# rev16.net
KiCad netlist of a schematic drawn in EAGLE
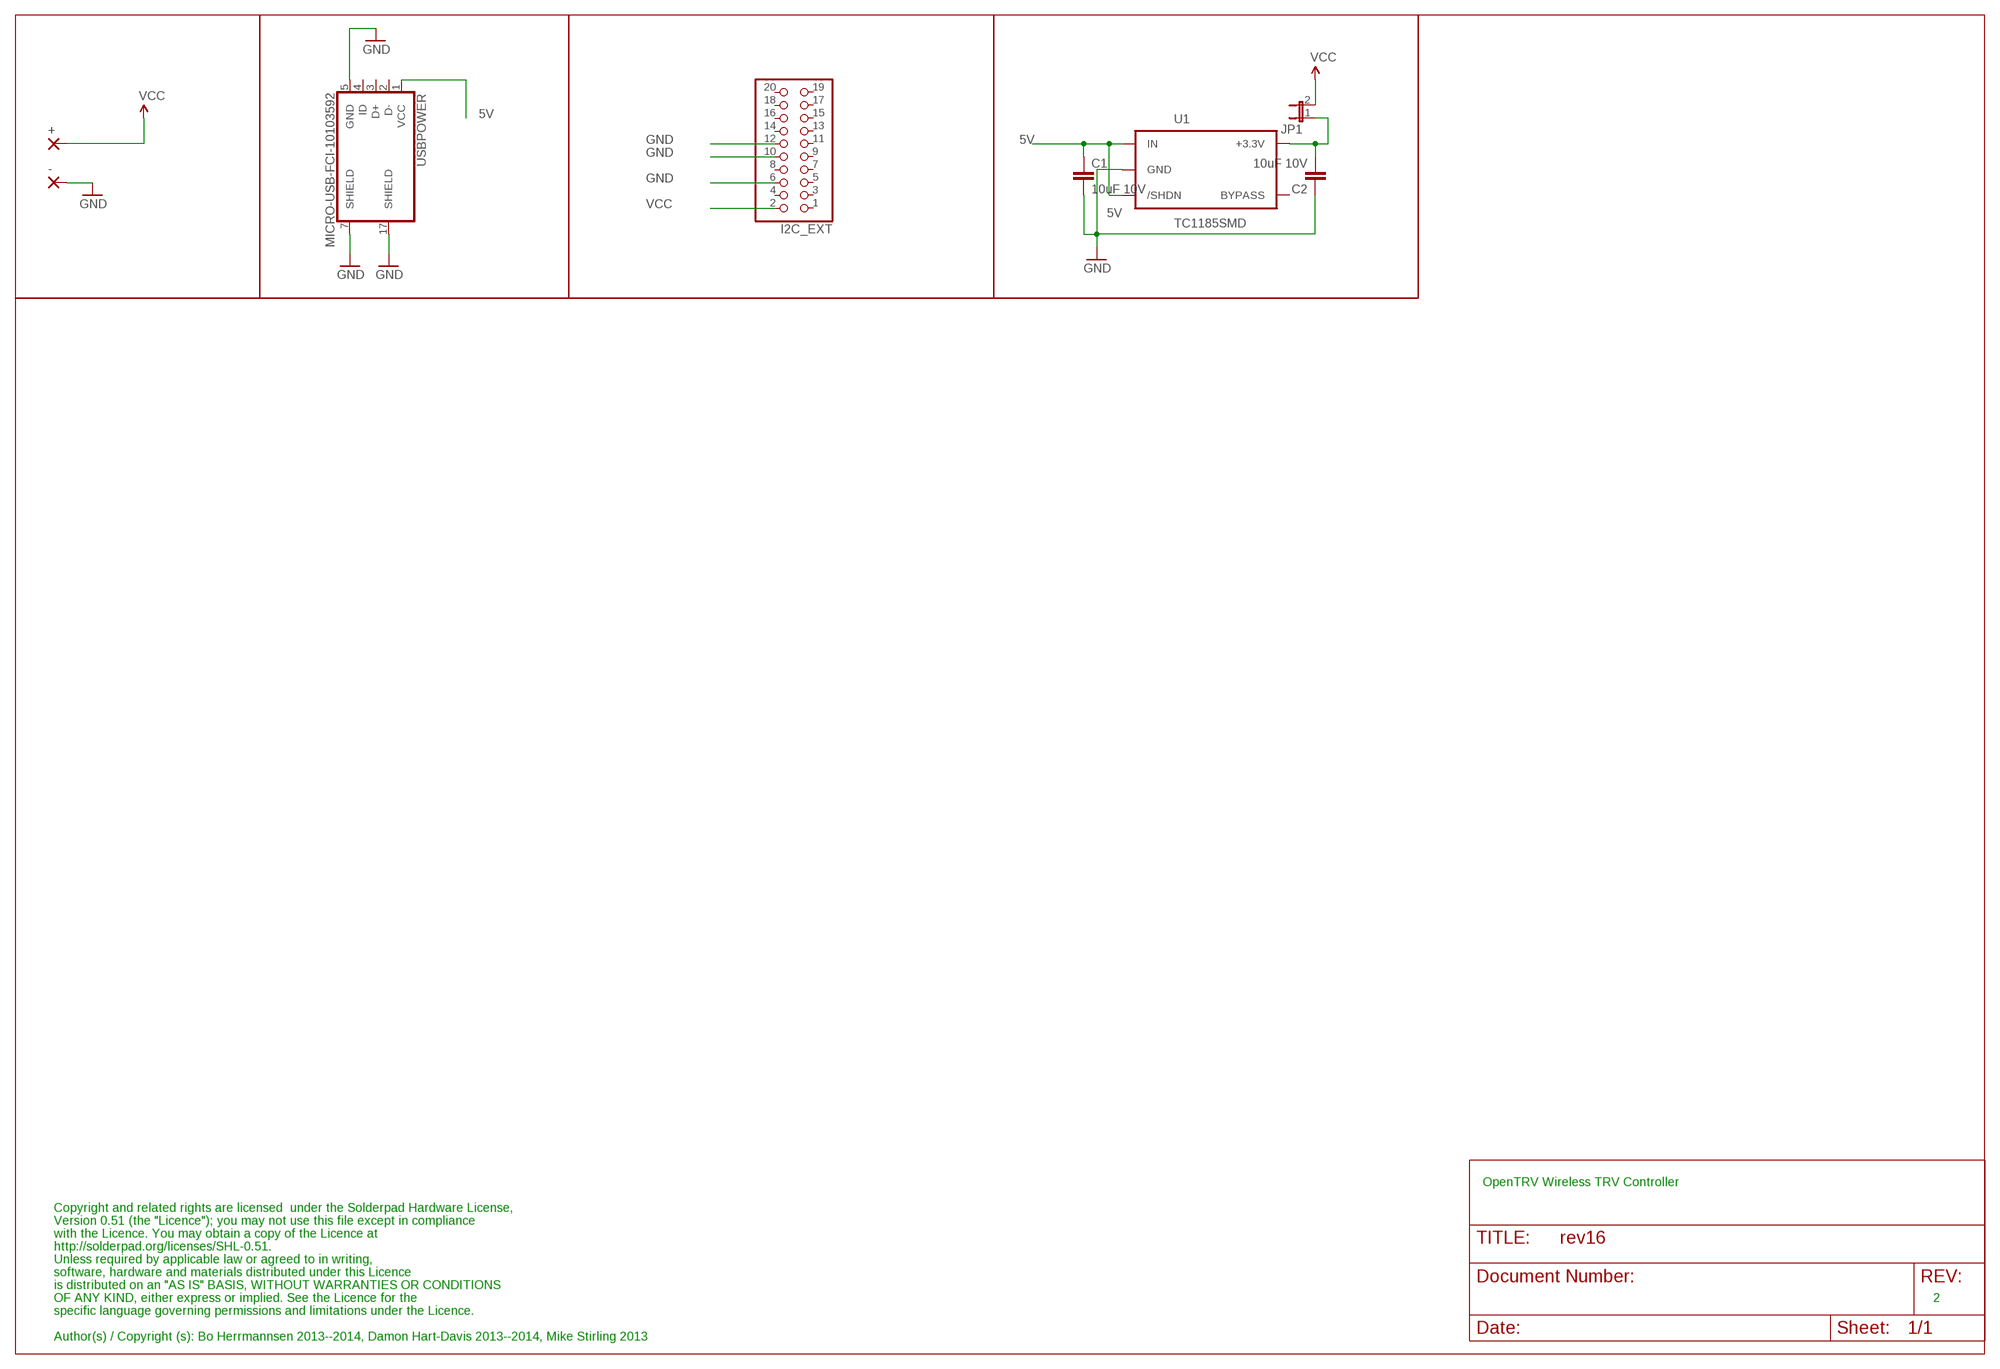
[diagram p0: schematic, sheet 1]

(export (version "E")
  (design (tool "Eeschema 10.0.6"))
  (components
    (comp (ref "+")
      (value "2,15/1,0")
      (footprint "eagle-import:2,15_1,0")
      (libsource (lib "eagle-import") (part "2,15/1,0"))
    )
    (comp (ref "-")
      (value "2,15/1,0")
      (footprint "eagle-import:2,15_1,0")
      (libsource (lib "eagle-import") (part "2,15/1,0"))
    )
    (comp (ref "C1")
      (value "10uF 10V")
      (footprint "eagle-import:0603-CAP")
      (libsource (lib "eagle-import") (part "CAP0603-CAP"))
    )
    (comp (ref "C2")
      (value "10uF 10V")
      (footprint "eagle-import:0603-CAP")
      (libsource (lib "eagle-import") (part "CAP0603-CAP"))
    )
    (comp (ref "I2C_EXT")
      (value "PINHD-2X10")
      (footprint "eagle-import:2X10")
      (libsource (lib "eagle-import") (part "PINHD-2X10"))
    )
    (comp (ref "JP1")
      (value "JP1E")
      (footprint "eagle-import:JP1")
      (libsource (lib "eagle-import") (part "JP1E"))
    )
    (comp (ref "U1")
      (value "TC1185SMD")
      (footprint "eagle-import:TC1185")
      (libsource (lib "eagle-import") (part "TC1185SMD"))
    )
    (comp (ref "USBPOWER")
      (value "MICRO-USB-FCI-10103592")
      (footprint "eagle-import:MICRO-USB-FCI-10103592")
      (libsource (lib "eagle-import") (part "MICRO-USB-FCI-10103592"))
    )
  )
  (nets
    (net (code "1") (name "/5V") (class "Default")
      (node (ref "C1") (pin "1") (pinfunction "1_1") (pintype "passive"))
      (node (ref "U1") (pin "1") (pinfunction "IN_1") (pintype "passive"))
      (node (ref "U1") (pin "3") (pinfunction "/SHDN_3") (pintype "passive"))
      (node (ref "USBPOWER") (pin "1") (pinfunction "VCC_1") (pintype "bidirectional"))
    )
    (net (code "2") (name "GND") (class "Default")
      (node (ref "-") (pin "1") (pinfunction "P_1") (pintype "passive"))
      (node (ref "C1") (pin "2") (pinfunction "2_2") (pintype "passive"))
      (node (ref "C2") (pin "1") (pinfunction "1_1") (pintype "passive"))
      (node (ref "I2C_EXT") (pin "10") (pinfunction "10_10") (pintype "passive"))
      (node (ref "I2C_EXT") (pin "12") (pinfunction "12_12") (pintype "passive"))
      (node (ref "I2C_EXT") (pin "6") (pinfunction "6_6") (pintype "passive"))
      (node (ref "U1") (pin "2") (pinfunction "GND_2") (pintype "passive"))
      (node (ref "USBPOWER") (pin "17") (pinfunction "SHIELD_17") (pintype "bidirectional"))
      (node (ref "USBPOWER") (pin "5") (pinfunction "GND_5") (pintype "bidirectional"))
      (node (ref "USBPOWER") (pin "7") (pinfunction "SHIELD_7") (pintype "bidirectional"))
    )
    (net (code "3") (name "Net-(U1-+3.3V)") (class "Default")
      (node (ref "C2") (pin "2") (pinfunction "2_2") (pintype "passive"))
      (node (ref "JP1") (pin "1") (pinfunction "1_1") (pintype "passive"))
      (node (ref "U1") (pin "5") (pinfunction "+3.3V_5") (pintype "power_in"))
    )
    (net (code "4") (name "VCC") (class "Default")
      (node (ref "+") (pin "1") (pinfunction "P_1") (pintype "passive"))
      (node (ref "I2C_EXT") (pin "2") (pinfunction "2_2") (pintype "passive"))
      (node (ref "JP1") (pin "2") (pinfunction "2_2") (pintype "passive"))
    )
    (net (code "5") (name "unconnected-(I2C_EXT-Pad1)") (class "Default")
      (node (ref "I2C_EXT") (pin "1") (pinfunction "1_1") (pintype "passive"))
    )
    (net (code "6") (name "unconnected-(I2C_EXT-Pad3)") (class "Default")
      (node (ref "I2C_EXT") (pin "3") (pinfunction "3_3") (pintype "passive"))
    )
    (net (code "7") (name "unconnected-(I2C_EXT-Pad4)") (class "Default")
      (node (ref "I2C_EXT") (pin "4") (pinfunction "4_4") (pintype "passive"))
    )
    (net (code "8") (name "unconnected-(I2C_EXT-Pad5)") (class "Default")
      (node (ref "I2C_EXT") (pin "5") (pinfunction "5_5") (pintype "passive"))
    )
    (net (code "9") (name "unconnected-(I2C_EXT-Pad7)") (class "Default")
      (node (ref "I2C_EXT") (pin "7") (pinfunction "7_7") (pintype "passive"))
    )
    (net (code "10") (name "unconnected-(I2C_EXT-Pad8)") (class "Default")
      (node (ref "I2C_EXT") (pin "8") (pinfunction "8_8") (pintype "passive"))
    )
    (net (code "11") (name "unconnected-(I2C_EXT-Pad9)") (class "Default")
      (node (ref "I2C_EXT") (pin "9") (pinfunction "9_9") (pintype "passive"))
    )
    (net (code "12") (name "unconnected-(I2C_EXT-Pad11)") (class "Default")
      (node (ref "I2C_EXT") (pin "11") (pinfunction "11_11") (pintype "passive"))
    )
    (net (code "13") (name "unconnected-(I2C_EXT-Pad13)") (class "Default")
      (node (ref "I2C_EXT") (pin "13") (pinfunction "13_13") (pintype "passive"))
    )
    (net (code "14") (name "unconnected-(I2C_EXT-Pad14)") (class "Default")
      (node (ref "I2C_EXT") (pin "14") (pinfunction "14_14") (pintype "passive"))
    )
    (net (code "15") (name "unconnected-(I2C_EXT-Pad15)") (class "Default")
      (node (ref "I2C_EXT") (pin "15") (pinfunction "15_15") (pintype "passive"))
    )
    (net (code "16") (name "unconnected-(I2C_EXT-Pad16)") (class "Default")
      (node (ref "I2C_EXT") (pin "16") (pinfunction "16_16") (pintype "passive"))
    )
    (net (code "17") (name "unconnected-(I2C_EXT-Pad17)") (class "Default")
      (node (ref "I2C_EXT") (pin "17") (pinfunction "17_17") (pintype "passive"))
    )
    (net (code "18") (name "unconnected-(I2C_EXT-Pad18)") (class "Default")
      (node (ref "I2C_EXT") (pin "18") (pinfunction "18_18") (pintype "passive"))
    )
    (net (code "19") (name "unconnected-(I2C_EXT-Pad19)") (class "Default")
      (node (ref "I2C_EXT") (pin "19") (pinfunction "19_19") (pintype "passive"))
    )
    (net (code "20") (name "unconnected-(I2C_EXT-Pad20)") (class "Default")
      (node (ref "I2C_EXT") (pin "20") (pinfunction "20_20") (pintype "passive"))
    )
    (net (code "21") (name "unconnected-(U1-BYPASS-Pad4)") (class "Default")
      (node (ref "U1") (pin "4") (pinfunction "BYPASS_4") (pintype "passive"))
    )
    (net (code "22") (name "unconnected-(USBPOWER-D+-Pad3)") (class "Default")
      (node (ref "USBPOWER") (pin "3") (pinfunction "D+_3") (pintype "bidirectional"))
    )
    (net (code "23") (name "unconnected-(USBPOWER-D--Pad2)") (class "Default")
      (node (ref "USBPOWER") (pin "2") (pinfunction "D-_2") (pintype "bidirectional"))
    )
    (net (code "24") (name "unconnected-(USBPOWER-ID-Pad4)") (class "Default")
      (node (ref "USBPOWER") (pin "4") (pinfunction "ID_4") (pintype "bidirectional"))
    )
  )
)
